# V3-POJ-STM32F103C8T6.net
KiCad netlist of a schematic drawn in EasyEDA Pro
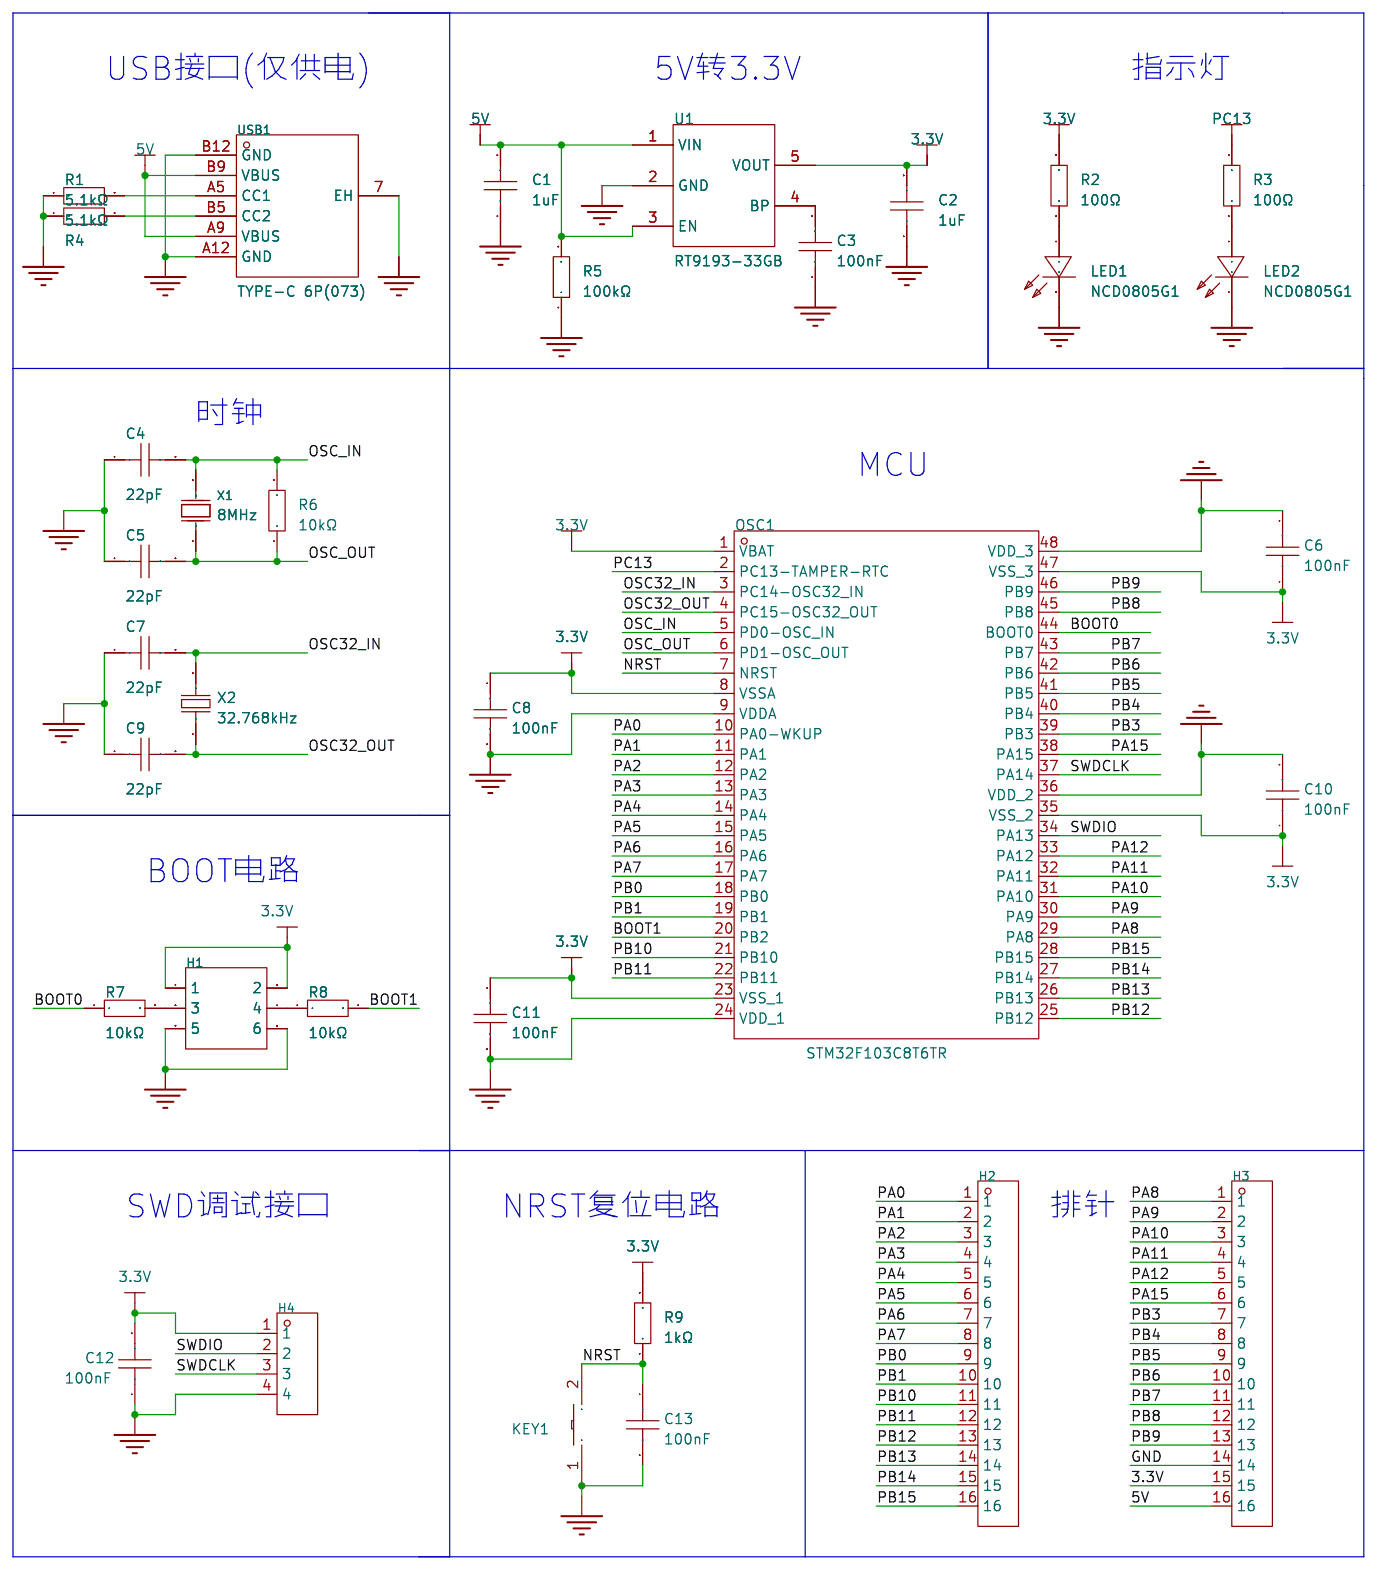
[diagram p0: schematic sheet]

(export (version "E")
  (design (tool "Eeschema 10.0.6"))
  (components
    (comp (ref "C1")
      (value "1uF")
      (footprint "easyedapro:C0603")
      (fields (field (name "Manufacturer Part") "0805B105K500NT") (field (name "Manufacturer") "FH(风华)"))
      (libsource (lib "easyedapro") (part "CapAcitance"))
    )
    (comp (ref "C2")
      (value "1uF")
      (footprint "easyedapro:C0603")
      (fields (field (name "Manufacturer Part") "0805B105K500NT") (field (name "Manufacturer") "FH(风华)"))
      (libsource (lib "easyedapro") (part "CapAcitance"))
    )
    (comp (ref "C3")
      (value "100nF")
      (footprint "easyedapro:C0603")
      (fields (field (name "Manufacturer Part") "0805B104K500NT") (field (name "Manufacturer") "FH(风华)"))
      (libsource (lib "easyedapro") (part "CapAcitance"))
    )
    (comp (ref "C4")
      (value "22pF")
      (footprint "easyedapro:C0805")
      (description "容值:22pF;精度:±5%;额定电压:50V;材质(温度系数):C0G;")
      (fields (field (name "Manufacturer Part") "0805CG220J500NT") (field (name "Manufacturer") "FH(风华)"))
      (libsource (lib "easyedapro") (part "0805CG220J500NT_C24658"))
    )
    (comp (ref "C5")
      (value "22pF")
      (footprint "easyedapro:C0805")
      (description "容值:22pF;精度:±5%;额定电压:50V;材质(温度系数):C0G;")
      (fields (field (name "Manufacturer Part") "0805CG220J500NT") (field (name "Manufacturer") "FH(风华)"))
      (libsource (lib "easyedapro") (part "0805CG220J500NT_C24658"))
    )
    (comp (ref "C6")
      (value "100nF")
      (footprint "easyedapro:C0603")
      (fields (field (name "Manufacturer Part") "0805B104K500NT") (field (name "Manufacturer") "FH(风华)"))
      (libsource (lib "easyedapro") (part "CapAcitance"))
    )
    (comp (ref "C7")
      (value "22pF")
      (footprint "easyedapro:C0805")
      (description "容值:22pF;精度:±5%;额定电压:50V;材质(温度系数):C0G;")
      (fields (field (name "Manufacturer Part") "0805CG220J500NT") (field (name "Manufacturer") "FH(风华)"))
      (libsource (lib "easyedapro") (part "0805CG220J500NT_C24658"))
    )
    (comp (ref "C8")
      (value "100nF")
      (footprint "easyedapro:C0603")
      (fields (field (name "Manufacturer Part") "0805B104K500NT") (field (name "Manufacturer") "FH(风华)"))
      (libsource (lib "easyedapro") (part "CapAcitance"))
    )
    (comp (ref "C9")
      (value "22pF")
      (footprint "easyedapro:C0805")
      (description "容值:22pF;精度:±5%;额定电压:50V;材质(温度系数):C0G;")
      (fields (field (name "Manufacturer Part") "0805CG220J500NT") (field (name "Manufacturer") "FH(风华)"))
      (libsource (lib "easyedapro") (part "0805CG220J500NT_C24658"))
    )
    (comp (ref "C10")
      (value "100nF")
      (footprint "easyedapro:C0603")
      (fields (field (name "Manufacturer Part") "0805B104K500NT") (field (name "Manufacturer") "FH(风华)"))
      (libsource (lib "easyedapro") (part "CapAcitance"))
    )
    (comp (ref "C11")
      (value "100nF")
      (footprint "easyedapro:C0603")
      (fields (field (name "Manufacturer Part") "0805B104K500NT") (field (name "Manufacturer") "FH(风华)"))
      (libsource (lib "easyedapro") (part "CapAcitance"))
    )
    (comp (ref "C12")
      (value "100nF")
      (footprint "easyedapro:C0603")
      (fields (field (name "Manufacturer Part") "0805B104K500NT") (field (name "Manufacturer") "FH(风华)"))
      (libsource (lib "easyedapro") (part "CapAcitance"))
    )
    (comp (ref "C13")
      (value "100nF")
      (footprint "easyedapro:C0603")
      (fields (field (name "Manufacturer Part") "0805B104K500NT") (field (name "Manufacturer") "FH(风华)"))
      (libsource (lib "easyedapro") (part "CapAcitance"))
    )
    (comp (ref "H1")
      (value "2.54-2*3P针")
      (footprint "easyedapro:HDR-TH_6P-P2.54-V-M-R2-C3-S2.54-1")
      (fields (field (name "Manufacturer") "BOOMELE(博穆精密)"))
      (libsource (lib "easyedapro") (part "Header-Male-2.54_2x3"))
    )
    (comp (ref "H2")
      (value "X6511WV-16H-C30D60")
      (footprint "easyedapro:HDR-TH_16P-P2.54-V-M")
      (fields (field (name "Manufacturer") "XKB Connectivity(中国星坤)"))
      (libsource (lib "easyedapro") (part "X6511WV-16H-C30D60"))
    )
    (comp (ref "H3")
      (value "X6511WV-16H-C30D60")
      (footprint "easyedapro:HDR-TH_16P-P2.54-V-M")
      (fields (field (name "Manufacturer") "XKB Connectivity(中国星坤)"))
      (libsource (lib "easyedapro") (part "X6511WV-16H-C30D60"))
    )
    (comp (ref "H4")
      (value "PZ254R-11-04P")
      (footprint "easyedapro:HDR-TH_4P-P2.54-V-M")
      (fields (field (name "Manufacturer") "XFCN(兴飞)"))
      (libsource (lib "easyedapro") (part "PZ254V-11-04P_C2691448"))
    )
    (comp (ref "KEY1")
      (value "TS-1101-C-W")
      (footprint "easyedapro:SW-SMD_L6.0-W3.3-LS8.0")
      (description "触点电流:50mA;额定电压(AC):-;额定电压(DC):12V;额定功率:-;绝缘电阻:-;电路结构:单刀单掷;安装方式:立贴;带灯:无;作用力:260gf;机械寿命:5万次;带支架:否;")
      (fields (field (name "Manufacturer") "XKB Connectivity(中国星坤)"))
      (libsource (lib "easyedapro") (part "TS-1101-C-W"))
    )
    (comp (ref "LED1")
      (value "NCD0805G1")
      (footprint "easyedapro:LED0805-R-RD")
      (description "发光颜色:翠绿;")
      (fields (field (name "Manufacturer") "国星光电"))
      (libsource (lib "easyedapro") (part "FC-2012UGK-520D5"))
    )
    (comp (ref "LED2")
      (value "NCD0805G1")
      (footprint "easyedapro:LED0805-R-RD")
      (description "发光颜色:翠绿;")
      (fields (field (name "Manufacturer") "国星光电"))
      (libsource (lib "easyedapro") (part "FC-2012UGK-520D5"))
    )
    (comp (ref "OSC1")
      (value "STM32F103C8T6TR")
      (footprint "easyedapro:LQFP-48_L7.0-W7.0-P0.50-LS9.0-BL")
      (fields (field (name "Manufacturer") "ST(意法半导体)"))
      (libsource (lib "easyedapro") (part "STM32F103C8T6TR"))
    )
    (comp (ref "R1")
      (value "5.1kΩ")
      (fields
        (field (name "Manufacturer Part") "0805W8F5101T5E")
        (field (name "Manufacturer") "UNI-ROYAL(厚声)")
      )
      (libsource (lib "easyedapro") (part "电阻"))
    )
    (comp (ref "R2")
      (value "100Ω")
      (footprint "easyedapro:R0603")
      (fields
        (field (name "Manufacturer Part") "0805W8F1000T5E")
        (field (name "Manufacturer") "UNI-ROYAL(厚声)")
      )
      (libsource (lib "easyedapro") (part "电阻"))
    )
    (comp (ref "R3")
      (value "100Ω")
      (footprint "easyedapro:R0603")
      (fields
        (field (name "Manufacturer Part") "0805W8F1000T5E")
        (field (name "Manufacturer") "UNI-ROYAL(厚声)")
      )
      (libsource (lib "easyedapro") (part "电阻"))
    )
    (comp (ref "R4")
      (value "5.1kΩ")
      (fields
        (field (name "Manufacturer Part") "0805W8F5101T5E")
        (field (name "Manufacturer") "UNI-ROYAL(厚声)")
      )
      (libsource (lib "easyedapro") (part "电阻"))
    )
    (comp (ref "R5")
      (value "100kΩ")
      (footprint "easyedapro:R0603")
      (fields
        (field (name "Manufacturer Part") "0805W8F1003T5E")
        (field (name "Manufacturer") "UNI-ROYAL(厚声)")
      )
      (libsource (lib "easyedapro") (part "电阻"))
    )
    (comp (ref "R6")
      (value "10kΩ")
      (footprint "easyedapro:R0805")
      (description "电阻类型:厚膜电阻;阻值:10kΩ;精度:±1%;功率:125mW;")
      (fields
        (field (name "Manufacturer Part") "0805W8F1002T5E")
        (field (name "Manufacturer") "UNI-ROYAL(厚声)")
      )
      (libsource (lib "easyedapro") (part "0805W8F1002T5E"))
    )
    (comp (ref "R7")
      (value "10kΩ")
      (footprint "easyedapro:R0603")
      (fields
        (field (name "Manufacturer Part") "0805W8F1002T5E")
        (field (name "Manufacturer") "UNI-ROYAL(厚声)")
      )
      (libsource (lib "easyedapro") (part "电阻"))
    )
    (comp (ref "R8")
      (value "10kΩ")
      (footprint "easyedapro:R0603")
      (fields
        (field (name "Manufacturer Part") "0805W8F1002T5E")
        (field (name "Manufacturer") "UNI-ROYAL(厚声)")
      )
      (libsource (lib "easyedapro") (part "电阻"))
    )
    (comp (ref "R9")
      (value "1kΩ")
      (footprint "easyedapro:R0603")
      (fields
        (field (name "Manufacturer Part") "0805W8F1001T5E")
        (field (name "Manufacturer") "UNI-ROYAL(厚声)")
      )
      (libsource (lib "easyedapro") (part "电阻"))
    )
    (comp (ref "U1")
      (value "RT9193-33GB")
      (footprint "easyedapro:SOT-23-5_L3.0-W1.7-P0.95-LS2.8-BL")
      (description "输出类型:固定;输出极性:正;输出通道数:1;最大输入电压:5.5V;输出电压:3.3V;压差:300mV@(300mA);输出电流:300mA;电源纹波抑制比(PSRR):70dB;")
      (fields (field (name "Manufacturer") "RICHTEK(立锜)"))
      (libsource (lib "easyedapro") (part "RT9193-33GB"))
    )
    (comp (ref "USB1")
      (value "TYPE-C 6P(073)")
      (footprint "easyedapro:TYPE-C-SMD_TYPE-C-6P")
      (description "连接器类型:Type-C;标准:-;公母:母座;触点数量:6P;端口数量:1;安装方式:卧贴;额定电流 - 电源:5A;工作温度范围:-25°C~+85°C;")
      (fields (field (name "Manufacturer") "SHOU HAN(首韩)"))
      (libsource (lib "easyedapro") (part "TYPE-C 6P(073)"))
    )
    (comp (ref "X1")
      (value "8MHz")
      (footprint "easyedapro:CRYSTAL-SMD_L5.0-W3.2")
      (description "频率:8MHz;频率公差:±10ppm;负载电容:20pF;")
      (fields (field (name "Manufacturer Part") "X50328MSB2GI") (field (name "Manufacturer") "YXC(扬兴晶振)"))
      (libsource (lib "easyedapro") (part "X50328MSB2GI"))
    )
    (comp (ref "X2")
      (value "32.768kHz")
      (footprint "easyedapro:FC-135R_L3.2-W1.5")
      (description "频率:32.768kHz;频率公差:±20ppm;负载电容:12.5pF;")
      (fields (field (name "Manufacturer Part") "Q13FC1350000400") (field (name "Manufacturer") "EPSON(爱普生)"))
      (libsource (lib "easyedapro") (part "Q13FC1350000400"))
    )
  )
  (nets
    (net (code "1") (name "/BOOT0") (class "Default")
      (node (ref "OSC1") (pin "44") (pinfunction "BOOT0_44") (pintype "input"))
      (node (ref "R7") (pin "1") (pinfunction "1_1") (pintype "input"))
    )
    (net (code "2") (name "/BOOT1") (class "Default")
      (node (ref "OSC1") (pin "20") (pinfunction "PB2_20") (pintype "input"))
      (node (ref "R8") (pin "2") (pinfunction "2_2") (pintype "input"))
    )
    (net (code "3") (name "/NRST") (class "Default")
      (node (ref "C13") (pin "1") (pinfunction "1_1") (pintype "input"))
      (node (ref "KEY1") (pin "2") (pinfunction "2_2") (pintype "input"))
      (node (ref "OSC1") (pin "7") (pinfunction "NRST_7") (pintype "input"))
      (node (ref "R9") (pin "1") (pinfunction "1_1") (pintype "input"))
    )
    (net (code "4") (name "/OSC32_IN") (class "Default")
      (node (ref "C7") (pin "2") (pinfunction "2_2") (pintype "input"))
      (node (ref "OSC1") (pin "3") (pinfunction "PC14-OSC32_IN_3") (pintype "input"))
      (node (ref "X2") (pin "2") (pinfunction "2_2") (pintype "input"))
    )
    (net (code "5") (name "/OSC32_OUT") (class "Default")
      (node (ref "C9") (pin "2") (pinfunction "2_2") (pintype "input"))
      (node (ref "OSC1") (pin "4") (pinfunction "PC15-OSC32_OUT_4") (pintype "input"))
      (node (ref "X2") (pin "1") (pinfunction "1_1") (pintype "input"))
    )
    (net (code "6") (name "/OSC_IN") (class "Default")
      (node (ref "C4") (pin "2") (pinfunction "2_2") (pintype "input"))
      (node (ref "OSC1") (pin "5") (pinfunction "PD0-OSC_IN_5") (pintype "input"))
      (node (ref "R6") (pin "2") (pinfunction "2_2") (pintype "input"))
      (node (ref "X1") (pin "2") (pinfunction "OSC2_2") (pintype "input"))
    )
    (net (code "7") (name "/OSC_OUT") (class "Default")
      (node (ref "C5") (pin "2") (pinfunction "2_2") (pintype "input"))
      (node (ref "OSC1") (pin "6") (pinfunction "PD1-OSC_OUT_6") (pintype "input"))
      (node (ref "R6") (pin "1") (pinfunction "1_1") (pintype "input"))
      (node (ref "X1") (pin "1") (pinfunction "OSC1_1") (pintype "input"))
    )
    (net (code "8") (name "/PA0") (class "Default")
      (node (ref "H2") (pin "1") (pinfunction "1_1") (pintype "input"))
      (node (ref "OSC1") (pin "10") (pinfunction "PA0-WKUP_10") (pintype "input"))
    )
    (net (code "9") (name "/PA1") (class "Default")
      (node (ref "H2") (pin "2") (pinfunction "2_2") (pintype "input"))
      (node (ref "OSC1") (pin "11") (pinfunction "PA1_11") (pintype "input"))
    )
    (net (code "10") (name "/PA2") (class "Default")
      (node (ref "H2") (pin "3") (pinfunction "3_3") (pintype "input"))
      (node (ref "OSC1") (pin "12") (pinfunction "PA2_12") (pintype "input"))
    )
    (net (code "11") (name "/PA3") (class "Default")
      (node (ref "H2") (pin "4") (pinfunction "4_4") (pintype "input"))
      (node (ref "OSC1") (pin "13") (pinfunction "PA3_13") (pintype "input"))
    )
    (net (code "12") (name "/PA4") (class "Default")
      (node (ref "H2") (pin "5") (pinfunction "5_5") (pintype "input"))
      (node (ref "OSC1") (pin "14") (pinfunction "PA4_14") (pintype "input"))
    )
    (net (code "13") (name "/PA5") (class "Default")
      (node (ref "H2") (pin "6") (pinfunction "6_6") (pintype "input"))
      (node (ref "OSC1") (pin "15") (pinfunction "PA5_15") (pintype "input"))
    )
    (net (code "14") (name "/PA6") (class "Default")
      (node (ref "H2") (pin "7") (pinfunction "7_7") (pintype "input"))
      (node (ref "OSC1") (pin "16") (pinfunction "PA6_16") (pintype "input"))
    )
    (net (code "15") (name "/PA7") (class "Default")
      (node (ref "H2") (pin "8") (pinfunction "8_8") (pintype "input"))
      (node (ref "OSC1") (pin "17") (pinfunction "PA7_17") (pintype "input"))
    )
    (net (code "16") (name "/PA8") (class "Default")
      (node (ref "H3") (pin "1") (pinfunction "1_1") (pintype "input"))
      (node (ref "OSC1") (pin "29") (pinfunction "PA8_29") (pintype "input"))
    )
    (net (code "17") (name "/PA9") (class "Default")
      (node (ref "H3") (pin "2") (pinfunction "2_2") (pintype "input"))
      (node (ref "OSC1") (pin "30") (pinfunction "PA9_30") (pintype "input"))
    )
    (net (code "18") (name "/PA10") (class "Default")
      (node (ref "H3") (pin "3") (pinfunction "3_3") (pintype "input"))
      (node (ref "OSC1") (pin "31") (pinfunction "PA10_31") (pintype "input"))
    )
    (net (code "19") (name "/PA11") (class "Default")
      (node (ref "H3") (pin "4") (pinfunction "4_4") (pintype "input"))
      (node (ref "OSC1") (pin "32") (pinfunction "PA11_32") (pintype "input"))
    )
    (net (code "20") (name "/PA12") (class "Default")
      (node (ref "H3") (pin "5") (pinfunction "5_5") (pintype "input"))
      (node (ref "OSC1") (pin "33") (pinfunction "PA12_33") (pintype "input"))
    )
    (net (code "21") (name "/PA15") (class "Default")
      (node (ref "H3") (pin "6") (pinfunction "6_6") (pintype "input"))
      (node (ref "OSC1") (pin "38") (pinfunction "PA15_38") (pintype "input"))
    )
    (net (code "22") (name "/PB0") (class "Default")
      (node (ref "H2") (pin "9") (pinfunction "9_9") (pintype "input"))
      (node (ref "OSC1") (pin "18") (pinfunction "PB0_18") (pintype "input"))
    )
    (net (code "23") (name "/PB1") (class "Default")
      (node (ref "H2") (pin "10") (pinfunction "10_10") (pintype "input"))
      (node (ref "OSC1") (pin "19") (pinfunction "PB1_19") (pintype "input"))
    )
    (net (code "24") (name "/PB3") (class "Default")
      (node (ref "H3") (pin "7") (pinfunction "7_7") (pintype "input"))
      (node (ref "OSC1") (pin "39") (pinfunction "PB3_39") (pintype "input"))
    )
    (net (code "25") (name "/PB4") (class "Default")
      (node (ref "H3") (pin "8") (pinfunction "8_8") (pintype "input"))
      (node (ref "OSC1") (pin "40") (pinfunction "PB4_40") (pintype "input"))
    )
    (net (code "26") (name "/PB5") (class "Default")
      (node (ref "H3") (pin "9") (pinfunction "9_9") (pintype "input"))
      (node (ref "OSC1") (pin "41") (pinfunction "PB5_41") (pintype "input"))
    )
    (net (code "27") (name "/PB6") (class "Default")
      (node (ref "H3") (pin "10") (pinfunction "10_10") (pintype "input"))
      (node (ref "OSC1") (pin "42") (pinfunction "PB6_42") (pintype "input"))
    )
    (net (code "28") (name "/PB7") (class "Default")
      (node (ref "H3") (pin "11") (pinfunction "11_11") (pintype "input"))
      (node (ref "OSC1") (pin "43") (pinfunction "PB7_43") (pintype "input"))
    )
    (net (code "29") (name "/PB8") (class "Default")
      (node (ref "H3") (pin "12") (pinfunction "12_12") (pintype "input"))
      (node (ref "OSC1") (pin "45") (pinfunction "PB8_45") (pintype "input"))
    )
    (net (code "30") (name "/PB9") (class "Default")
      (node (ref "H3") (pin "13") (pinfunction "13_13") (pintype "input"))
      (node (ref "OSC1") (pin "46") (pinfunction "PB9_46") (pintype "input"))
    )
    (net (code "31") (name "/PB10") (class "Default")
      (node (ref "H2") (pin "11") (pinfunction "11_11") (pintype "input"))
      (node (ref "OSC1") (pin "21") (pinfunction "PB10_21") (pintype "input"))
    )
    (net (code "32") (name "/PB11") (class "Default")
      (node (ref "H2") (pin "12") (pinfunction "12_12") (pintype "input"))
      (node (ref "OSC1") (pin "22") (pinfunction "PB11_22") (pintype "input"))
    )
    (net (code "33") (name "/PB12") (class "Default")
      (node (ref "H2") (pin "13") (pinfunction "13_13") (pintype "input"))
      (node (ref "OSC1") (pin "25") (pinfunction "PB12_25") (pintype "input"))
    )
    (net (code "34") (name "/PB13") (class "Default")
      (node (ref "H2") (pin "14") (pinfunction "14_14") (pintype "input"))
      (node (ref "OSC1") (pin "26") (pinfunction "PB13_26") (pintype "input"))
    )
    (net (code "35") (name "/PB14") (class "Default")
      (node (ref "H2") (pin "15") (pinfunction "15_15") (pintype "input"))
      (node (ref "OSC1") (pin "27") (pinfunction "PB14_27") (pintype "input"))
    )
    (net (code "36") (name "/PB15") (class "Default")
      (node (ref "H2") (pin "16") (pinfunction "16_16") (pintype "input"))
      (node (ref "OSC1") (pin "28") (pinfunction "PB15_28") (pintype "input"))
    )
    (net (code "37") (name "/SWDCLK") (class "Default")
      (node (ref "H4") (pin "3") (pinfunction "3_3") (pintype "input"))
      (node (ref "OSC1") (pin "37") (pinfunction "PA14_37") (pintype "input"))
    )
    (net (code "38") (name "/SWDIO") (class "Default")
      (node (ref "H4") (pin "2") (pinfunction "2_2") (pintype "input"))
      (node (ref "OSC1") (pin "34") (pinfunction "PA13_34") (pintype "input"))
    )
    (net (code "39") (name "3.3V") (class "Default")
      (node (ref "C10") (pin "1") (pinfunction "1_1") (pintype "input"))
      (node (ref "C11") (pin "1") (pinfunction "1_1") (pintype "input"))
      (node (ref "C12") (pin "2") (pinfunction "2_2") (pintype "input"))
      (node (ref "C2") (pin "2") (pinfunction "2_2") (pintype "input"))
      (node (ref "C6") (pin "1") (pinfunction "1_1") (pintype "input"))
      (node (ref "C8") (pin "1") (pinfunction "1_1") (pintype "input"))
      (node (ref "H1") (pin "1") (pinfunction "1_1") (pintype "input"))
      (node (ref "H1") (pin "2") (pinfunction "2_2") (pintype "input"))
      (node (ref "H3") (pin "15") (pinfunction "15_15") (pintype "input"))
      (node (ref "H4") (pin "1") (pinfunction "1_1") (pintype "input"))
      (node (ref "OSC1") (pin "1") (pinfunction "VBAT_1") (pintype "input"))
      (node (ref "OSC1") (pin "23") (pinfunction "VSS_1_23") (pintype "input"))
      (node (ref "OSC1") (pin "35") (pinfunction "VSS_2_35") (pintype "input"))
      (node (ref "OSC1") (pin "47") (pinfunction "VSS_3_47") (pintype "input"))
      (node (ref "OSC1") (pin "8") (pinfunction "VSSA_8") (pintype "input"))
      (node (ref "R2") (pin "2") (pinfunction "2_2") (pintype "input"))
      (node (ref "R9") (pin "2") (pinfunction "2_2") (pintype "input"))
      (node (ref "U1") (pin "5") (pinfunction "VOUT_5") (pintype "input"))
    )
    (net (code "40") (name "5V") (class "Default")
      (node (ref "C1") (pin "2") (pinfunction "2_2") (pintype "input"))
      (node (ref "H3") (pin "16") (pinfunction "16_16") (pintype "input"))
      (node (ref "R5") (pin "2") (pinfunction "2_2") (pintype "input"))
      (node (ref "U1") (pin "1") (pinfunction "VIN_1") (pintype "input"))
      (node (ref "U1") (pin "3") (pinfunction "EN_3") (pintype "input"))
      (node (ref "USB1") (pin "A9") (pinfunction "VBUS_A9") (pintype "input"))
      (node (ref "USB1") (pin "B9") (pinfunction "VBUS_B9") (pintype "input"))
    )
    (net (code "41") (name "GND") (class "Default")
      (node (ref "C1") (pin "1") (pinfunction "1_1") (pintype "input"))
      (node (ref "C10") (pin "2") (pinfunction "2_2") (pintype "input"))
      (node (ref "C11") (pin "2") (pinfunction "2_2") (pintype "input"))
      (node (ref "C12") (pin "1") (pinfunction "1_1") (pintype "input"))
      (node (ref "C13") (pin "2") (pinfunction "2_2") (pintype "input"))
      (node (ref "C2") (pin "1") (pinfunction "1_1") (pintype "input"))
      (node (ref "C3") (pin "1") (pinfunction "1_1") (pintype "input"))
      (node (ref "C4") (pin "1") (pinfunction "1_1") (pintype "input"))
      (node (ref "C5") (pin "1") (pinfunction "1_1") (pintype "input"))
      (node (ref "C6") (pin "2") (pinfunction "2_2") (pintype "input"))
      (node (ref "C7") (pin "1") (pinfunction "1_1") (pintype "input"))
      (node (ref "C8") (pin "2") (pinfunction "2_2") (pintype "input"))
      (node (ref "C9") (pin "1") (pinfunction "1_1") (pintype "input"))
      (node (ref "H1") (pin "5") (pinfunction "5_5") (pintype "input"))
      (node (ref "H1") (pin "6") (pinfunction "6_6") (pintype "input"))
      (node (ref "H3") (pin "14") (pinfunction "14_14") (pintype "input"))
      (node (ref "H4") (pin "4") (pinfunction "4_4") (pintype "input"))
      (node (ref "KEY1") (pin "1") (pinfunction "1_1") (pintype "input"))
      (node (ref "LED1") (pin "2") (pinfunction "K_2") (pintype "unspecified"))
      (node (ref "LED2") (pin "2") (pinfunction "K_2") (pintype "unspecified"))
      (node (ref "OSC1") (pin "24") (pinfunction "VDD_1_24") (pintype "input"))
      (node (ref "OSC1") (pin "36") (pinfunction "VDD_2_36") (pintype "input"))
      (node (ref "OSC1") (pin "48") (pinfunction "VDD_3_48") (pintype "input"))
      (node (ref "OSC1") (pin "9") (pinfunction "VDDA_9") (pintype "input"))
      (node (ref "R1") (pin "1") (pinfunction "1_1") (pintype "input"))
      (node (ref "R4") (pin "1") (pinfunction "1_1") (pintype "input"))
      (node (ref "R5") (pin "1") (pinfunction "1_1") (pintype "input"))
      (node (ref "U1") (pin "2") (pinfunction "GND_2") (pintype "input"))
      (node (ref "USB1") (pin "7") (pinfunction "EH_7") (pintype "input"))
      (node (ref "USB1") (pin "A12") (pinfunction "GND_A12") (pintype "input"))
      (node (ref "USB1") (pin "B12") (pinfunction "GND_B12") (pintype "input"))
    )
    (net (code "42") (name "Net-(H1-Pad3)") (class "Default")
      (node (ref "H1") (pin "3") (pinfunction "3_3") (pintype "input"))
      (node (ref "R7") (pin "2") (pinfunction "2_2") (pintype "input"))
    )
    (net (code "43") (name "Net-(H1-Pad4)") (class "Default")
      (node (ref "H1") (pin "4") (pinfunction "4_4") (pintype "input"))
      (node (ref "R8") (pin "1") (pinfunction "1_1") (pintype "input"))
    )
    (net (code "44") (name "Net-(LED1-A)") (class "Default")
      (node (ref "LED1") (pin "1") (pinfunction "A_1") (pintype "unspecified"))
      (node (ref "R2") (pin "1") (pinfunction "1_1") (pintype "input"))
    )
    (net (code "45") (name "Net-(LED2-A)") (class "Default")
      (node (ref "LED2") (pin "1") (pinfunction "A_1") (pintype "unspecified"))
      (node (ref "R3") (pin "1") (pinfunction "1_1") (pintype "input"))
    )
    (net (code "46") (name "Net-(U1-BP)") (class "Default")
      (node (ref "C3") (pin "2") (pinfunction "2_2") (pintype "input"))
      (node (ref "U1") (pin "4") (pinfunction "BP_4") (pintype "input"))
    )
    (net (code "47") (name "Net-(USB1-CC1)") (class "Default")
      (node (ref "R1") (pin "2") (pinfunction "2_2") (pintype "input"))
      (node (ref "USB1") (pin "A5") (pinfunction "CC1_A5") (pintype "input"))
    )
    (net (code "48") (name "Net-(USB1-CC2)") (class "Default")
      (node (ref "R4") (pin "2") (pinfunction "2_2") (pintype "input"))
      (node (ref "USB1") (pin "B5") (pinfunction "CC2_B5") (pintype "input"))
    )
    (net (code "49") (name "PC13") (class "Default")
      (node (ref "OSC1") (pin "2") (pinfunction "PC13-TAMPER-RTC_2") (pintype "input"))
      (node (ref "R3") (pin "2") (pinfunction "2_2") (pintype "input"))
    )
  )
)
